# line_adapter.net
KiCad netlist of a schematic drawn in EAGLE
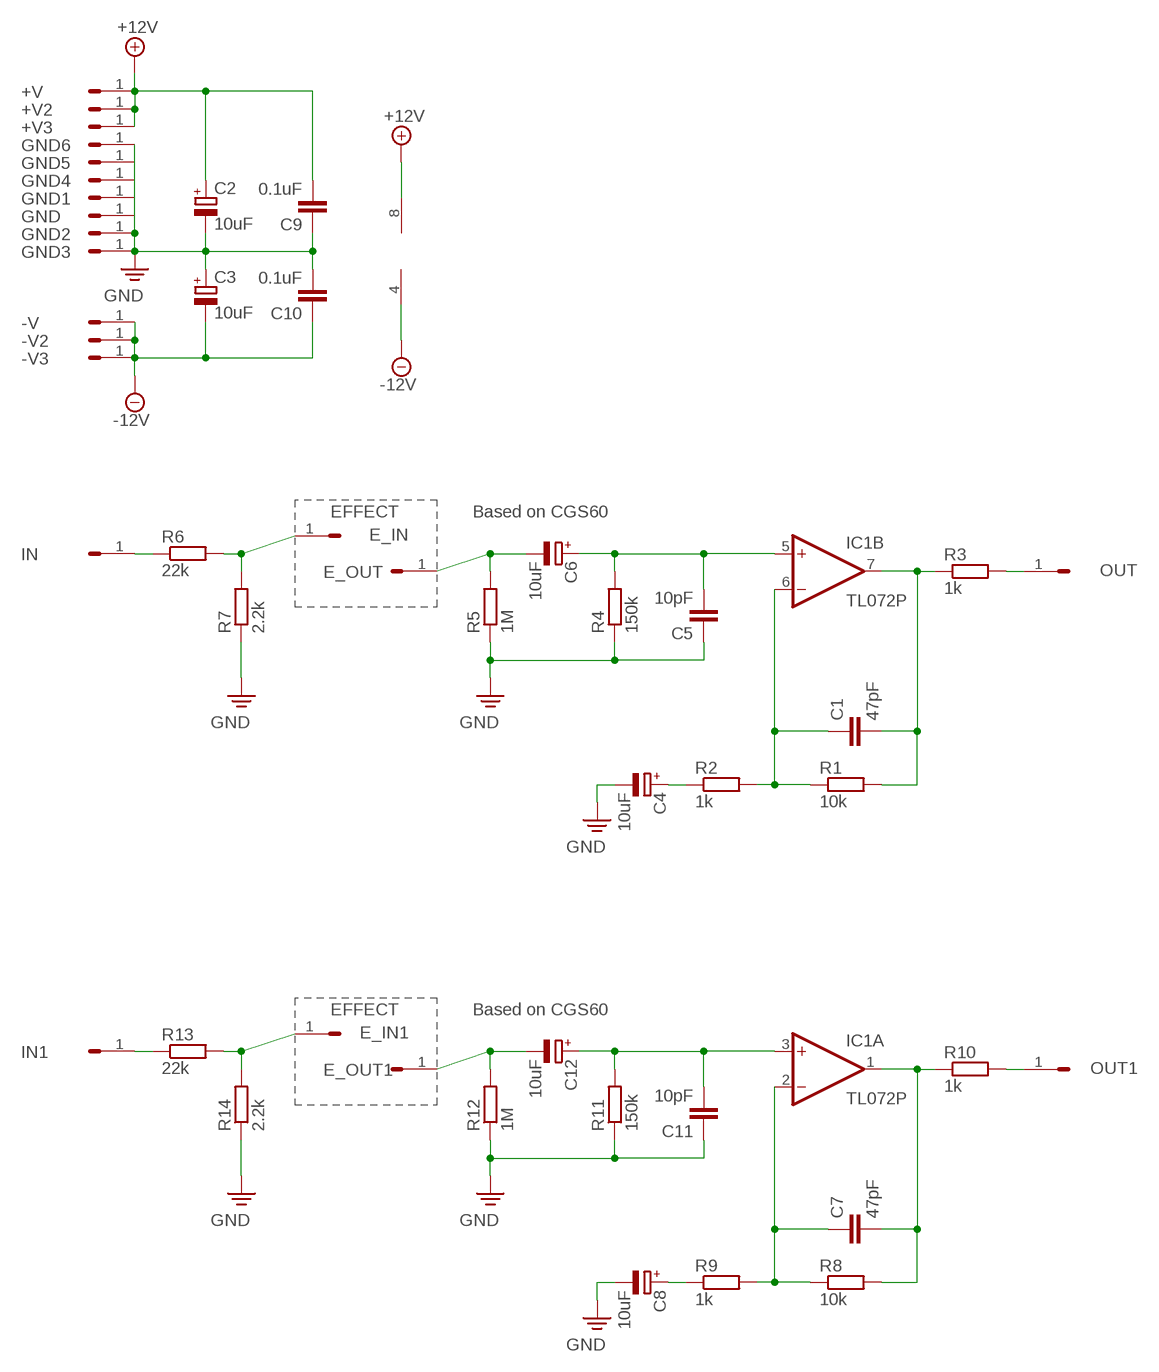
[diagram p0: schematic, sheet 1]

(export (version "E")
  (design (tool "Eeschema 10.0.6"))
  (components
    (comp (ref "+V")
      (value "HEADER/MALE/01")
      (footprint "eagle-import:HEADER_MALE_01")
      (fields (field (name "SPICEPREFIX") "X"))
      (libsource (lib "eagle-import") (part "HEADER/MALE/01"))
    )
    (comp (ref "+V2")
      (value "HEADER/MALE/01")
      (footprint "eagle-import:HEADER_MALE_01")
      (fields (field (name "SPICEPREFIX") "X"))
      (libsource (lib "eagle-import") (part "HEADER/MALE/01"))
    )
    (comp (ref "+V3")
      (value "HEADER/MALE/01")
      (footprint "eagle-import:HEADER_MALE_01")
      (fields (field (name "SPICEPREFIX") "X"))
      (libsource (lib "eagle-import") (part "HEADER/MALE/01"))
    )
    (comp (ref "-V")
      (value "HEADER/MALE/01")
      (footprint "eagle-import:HEADER_MALE_01")
      (fields (field (name "SPICEPREFIX") "X"))
      (libsource (lib "eagle-import") (part "HEADER/MALE/01"))
    )
    (comp (ref "-V2")
      (value "HEADER/MALE/01")
      (footprint "eagle-import:HEADER_MALE_01")
      (fields (field (name "SPICEPREFIX") "X"))
      (libsource (lib "eagle-import") (part "HEADER/MALE/01"))
    )
    (comp (ref "-V3")
      (value "HEADER/MALE/01")
      (footprint "eagle-import:HEADER_MALE_01")
      (fields (field (name "SPICEPREFIX") "X"))
      (libsource (lib "eagle-import") (part "HEADER/MALE/01"))
    )
    (comp (ref "C1")
      (value "47pF")
      (footprint "eagle-import:CERAMICDISC_5")
      (libsource (lib "eagle-import") (part "CAPACITORCERAMICDISC/5"))
    )
    (comp (ref "C2")
      (value "10uF")
      (footprint "eagle-import:E2,5-6")
      (fields (field (name "SPICEPREFIX") "C"))
      (libsource (lib "eagle-import") (part "CAPACITOR/POLARIZEDE2.5-6"))
    )
    (comp (ref "C3")
      (value "10uF")
      (footprint "eagle-import:E2,5-6")
      (fields (field (name "SPICEPREFIX") "C"))
      (libsource (lib "eagle-import") (part "CAPACITOR/POLARIZEDE2.5-6"))
    )
    (comp (ref "C4")
      (value "10uF")
      (footprint "eagle-import:E2,5-6")
      (fields (field (name "SPICEPREFIX") "C"))
      (libsource (lib "eagle-import") (part "CAPACITOR/POLARIZEDE2.5-6"))
    )
    (comp (ref "C5")
      (value "10pF")
      (footprint "eagle-import:CERAMICDISC_5")
      (libsource (lib "eagle-import") (part "CAPACITORCERAMICDISC/5"))
    )
    (comp (ref "C6")
      (value "10uF")
      (footprint "eagle-import:E2,5-6")
      (fields (field (name "SPICEPREFIX") "C"))
      (libsource (lib "eagle-import") (part "CAPACITOR/POLARIZEDE2.5-6"))
    )
    (comp (ref "C7")
      (value "47pF")
      (footprint "eagle-import:CERAMICDISC_5")
      (libsource (lib "eagle-import") (part "CAPACITORCERAMICDISC/5"))
    )
    (comp (ref "C8")
      (value "10uF")
      (footprint "eagle-import:E2,5-6")
      (fields (field (name "SPICEPREFIX") "C"))
      (libsource (lib "eagle-import") (part "CAPACITOR/POLARIZEDE2.5-6"))
    )
    (comp (ref "C9")
      (value "0.1uF")
      (footprint "eagle-import:CERAMICDISC_5")
      (libsource (lib "eagle-import") (part "CAPACITORCERAMICDISC/5"))
    )
    (comp (ref "C10")
      (value "0.1uF")
      (footprint "eagle-import:CERAMICDISC_5")
      (libsource (lib "eagle-import") (part "CAPACITORCERAMICDISC/5"))
    )
    (comp (ref "C11")
      (value "10pF")
      (footprint "eagle-import:CERAMICDISC_5")
      (libsource (lib "eagle-import") (part "CAPACITORCERAMICDISC/5"))
    )
    (comp (ref "C12")
      (value "10uF")
      (footprint "eagle-import:E2,5-6")
      (fields (field (name "SPICEPREFIX") "C"))
      (libsource (lib "eagle-import") (part "CAPACITOR/POLARIZEDE2.5-6"))
    )
    (comp (ref "E_IN")
      (value "HEADER/MALE/01")
      (footprint "eagle-import:HEADER_MALE_01")
      (fields (field (name "SPICEPREFIX") "X"))
      (libsource (lib "eagle-import") (part "HEADER/MALE/01"))
    )
    (comp (ref "E_IN1")
      (value "HEADER/MALE/01")
      (footprint "eagle-import:HEADER_MALE_01")
      (fields (field (name "SPICEPREFIX") "X"))
      (libsource (lib "eagle-import") (part "HEADER/MALE/01"))
    )
    (comp (ref "E_OUT")
      (value "HEADER/MALE/01")
      (footprint "eagle-import:HEADER_MALE_01")
      (fields (field (name "SPICEPREFIX") "X"))
      (libsource (lib "eagle-import") (part "HEADER/MALE/01"))
    )
    (comp (ref "E_OUT1")
      (value "HEADER/MALE/01")
      (footprint "eagle-import:HEADER_MALE_01")
      (fields (field (name "SPICEPREFIX") "X"))
      (libsource (lib "eagle-import") (part "HEADER/MALE/01"))
    )
    (comp (ref "GND")
      (value "HEADER/MALE/01")
      (footprint "eagle-import:HEADER_MALE_01")
      (fields (field (name "SPICEPREFIX") "X"))
      (libsource (lib "eagle-import") (part "HEADER/MALE/01"))
    )
    (comp (ref "GND1")
      (value "HEADER/MALE/01")
      (footprint "eagle-import:HEADER_MALE_01")
      (fields (field (name "SPICEPREFIX") "X"))
      (libsource (lib "eagle-import") (part "HEADER/MALE/01"))
    )
    (comp (ref "GND2")
      (value "HEADER/MALE/01")
      (footprint "eagle-import:HEADER_MALE_01")
      (fields (field (name "SPICEPREFIX") "X"))
      (libsource (lib "eagle-import") (part "HEADER/MALE/01"))
    )
    (comp (ref "GND3")
      (value "HEADER/MALE/01")
      (footprint "eagle-import:HEADER_MALE_01")
      (fields (field (name "SPICEPREFIX") "X"))
      (libsource (lib "eagle-import") (part "HEADER/MALE/01"))
    )
    (comp (ref "GND4")
      (value "HEADER/MALE/01")
      (footprint "eagle-import:HEADER_MALE_01")
      (fields (field (name "SPICEPREFIX") "X"))
      (libsource (lib "eagle-import") (part "HEADER/MALE/01"))
    )
    (comp (ref "GND5")
      (value "HEADER/MALE/01")
      (footprint "eagle-import:HEADER_MALE_01")
      (fields (field (name "SPICEPREFIX") "X"))
      (libsource (lib "eagle-import") (part "HEADER/MALE/01"))
    )
    (comp (ref "GND6")
      (value "HEADER/MALE/01")
      (footprint "eagle-import:HEADER_MALE_01")
      (fields (field (name "SPICEPREFIX") "X"))
      (libsource (lib "eagle-import") (part "HEADER/MALE/01"))
    )
    (comp (ref "IC1")
      (value "TL072P")
      (footprint "eagle-import:DIL08")
      (libsource (lib "eagle-import") (part "TL072P"))
    )
    (comp (ref "IN")
      (value "HEADER/MALE/01")
      (footprint "eagle-import:HEADER_MALE_01")
      (fields (field (name "SPICEPREFIX") "X"))
      (libsource (lib "eagle-import") (part "HEADER/MALE/01"))
    )
    (comp (ref "IN1")
      (value "HEADER/MALE/01")
      (footprint "eagle-import:HEADER_MALE_01")
      (fields (field (name "SPICEPREFIX") "X"))
      (libsource (lib "eagle-import") (part "HEADER/MALE/01"))
    )
    (comp (ref "OUT")
      (value "HEADER/MALE/01")
      (footprint "eagle-import:HEADER_MALE_01")
      (fields (field (name "SPICEPREFIX") "X"))
      (libsource (lib "eagle-import") (part "HEADER/MALE/01"))
    )
    (comp (ref "OUT1")
      (value "HEADER/MALE/01")
      (footprint "eagle-import:HEADER_MALE_01")
      (fields (field (name "SPICEPREFIX") "X"))
      (libsource (lib "eagle-import") (part "HEADER/MALE/01"))
    )
    (comp (ref "R1")
      (value "10k")
      (footprint "eagle-import:RESISTOR_7.5")
      (libsource (lib "eagle-import") (part "RESISTORRESISTOR/UPRIGHT/7.5"))
    )
    (comp (ref "R2")
      (value "1k")
      (footprint "eagle-import:RESISTOR_7.5")
      (libsource (lib "eagle-import") (part "RESISTORRESISTOR/UPRIGHT/7.5"))
    )
    (comp (ref "R3")
      (value "1k")
      (footprint "eagle-import:RESISTOR_7.5")
      (libsource (lib "eagle-import") (part "RESISTORRESISTOR/UPRIGHT/7.5"))
    )
    (comp (ref "R4")
      (value "150k")
      (footprint "eagle-import:RESISTOR_7.5")
      (libsource (lib "eagle-import") (part "RESISTORRESISTOR/UPRIGHT/7.5"))
    )
    (comp (ref "R5")
      (value "1M")
      (footprint "eagle-import:RESISTOR_7.5")
      (libsource (lib "eagle-import") (part "RESISTORRESISTOR/UPRIGHT/7.5"))
    )
    (comp (ref "R6")
      (value "22k")
      (footprint "eagle-import:RESISTOR_7.5")
      (libsource (lib "eagle-import") (part "RESISTORRESISTOR/UPRIGHT/7.5"))
    )
    (comp (ref "R7")
      (value "2.2k")
      (footprint "eagle-import:RESISTOR_7.5")
      (libsource (lib "eagle-import") (part "RESISTORRESISTOR/UPRIGHT/7.5"))
    )
    (comp (ref "R8")
      (value "10k")
      (footprint "eagle-import:RESISTOR_7.5")
      (libsource (lib "eagle-import") (part "RESISTORRESISTOR/UPRIGHT/7.5"))
    )
    (comp (ref "R9")
      (value "1k")
      (footprint "eagle-import:RESISTOR_7.5")
      (libsource (lib "eagle-import") (part "RESISTORRESISTOR/UPRIGHT/7.5"))
    )
    (comp (ref "R10")
      (value "1k")
      (footprint "eagle-import:RESISTOR_7.5")
      (libsource (lib "eagle-import") (part "RESISTORRESISTOR/UPRIGHT/7.5"))
    )
    (comp (ref "R11")
      (value "150k")
      (footprint "eagle-import:RESISTOR_7.5")
      (libsource (lib "eagle-import") (part "RESISTORRESISTOR/UPRIGHT/7.5"))
    )
    (comp (ref "R12")
      (value "1M")
      (footprint "eagle-import:RESISTOR_7.5")
      (libsource (lib "eagle-import") (part "RESISTORRESISTOR/UPRIGHT/7.5"))
    )
    (comp (ref "R13")
      (value "22k")
      (footprint "eagle-import:RESISTOR_7.5")
      (libsource (lib "eagle-import") (part "RESISTORRESISTOR/UPRIGHT/7.5"))
    )
    (comp (ref "R14")
      (value "2.2k")
      (footprint "eagle-import:RESISTOR_7.5")
      (libsource (lib "eagle-import") (part "RESISTORRESISTOR/UPRIGHT/7.5"))
    )
  )
  (nets
    (net (code "1") (name "+12V") (class "Default")
      (node (ref "+V") (pin "1") (pinfunction "3_1") (pintype "passive"))
      (node (ref "+V2") (pin "1") (pinfunction "3_1") (pintype "passive"))
      (node (ref "+V3") (pin "1") (pinfunction "3_1") (pintype "passive"))
      (node (ref "C2") (pin "+") (pinfunction "+_+") (pintype "passive"))
      (node (ref "C9") (pin "2") (pinfunction "2_2") (pintype "passive"))
      (node (ref "IC1") (pin "8") (pinfunction "V+_8") (pintype "power_in"))
    )
    (net (code "2") (name "-12V") (class "Default")
      (node (ref "-V") (pin "1") (pinfunction "3_1") (pintype "passive"))
      (node (ref "-V2") (pin "1") (pinfunction "3_1") (pintype "passive"))
      (node (ref "-V3") (pin "1") (pinfunction "3_1") (pintype "passive"))
      (node (ref "C10") (pin "1") (pinfunction "1_1") (pintype "passive"))
      (node (ref "C3") (pin "-") (pinfunction "-_-") (pintype "passive"))
      (node (ref "IC1") (pin "4") (pinfunction "V-_4") (pintype "power_in"))
    )
    (net (code "3") (name "GND") (class "Default")
      (node (ref "C10") (pin "2") (pinfunction "2_2") (pintype "passive"))
      (node (ref "C11") (pin "1") (pinfunction "1_1") (pintype "passive"))
      (node (ref "C2") (pin "-") (pinfunction "-_-") (pintype "passive"))
      (node (ref "C3") (pin "+") (pinfunction "+_+") (pintype "passive"))
      (node (ref "C4") (pin "-") (pinfunction "-_-") (pintype "passive"))
      (node (ref "C5") (pin "1") (pinfunction "1_1") (pintype "passive"))
      (node (ref "C8") (pin "-") (pinfunction "-_-") (pintype "passive"))
      (node (ref "C9") (pin "1") (pinfunction "1_1") (pintype "passive"))
      (node (ref "GND") (pin "1") (pinfunction "3_1") (pintype "passive"))
      (node (ref "GND1") (pin "1") (pinfunction "3_1") (pintype "passive"))
      (node (ref "GND2") (pin "1") (pinfunction "3_1") (pintype "passive"))
      (node (ref "GND3") (pin "1") (pinfunction "3_1") (pintype "passive"))
      (node (ref "GND4") (pin "1") (pinfunction "3_1") (pintype "passive"))
      (node (ref "GND5") (pin "1") (pinfunction "3_1") (pintype "passive"))
      (node (ref "GND6") (pin "1") (pinfunction "3_1") (pintype "passive"))
      (node (ref "R11") (pin "1") (pinfunction "1_1") (pintype "passive"))
      (node (ref "R12") (pin "1") (pinfunction "1_1") (pintype "passive"))
      (node (ref "R14") (pin "1") (pinfunction "1_1") (pintype "passive"))
      (node (ref "R4") (pin "1") (pinfunction "1_1") (pintype "passive"))
      (node (ref "R5") (pin "1") (pinfunction "1_1") (pintype "passive"))
      (node (ref "R7") (pin "1") (pinfunction "1_1") (pintype "passive"))
    )
    (net (code "4") (name "Net-(C4-Pad+)") (class "Default")
      (node (ref "C4") (pin "+") (pinfunction "+_+") (pintype "passive"))
      (node (ref "R2") (pin "1") (pinfunction "1_1") (pintype "passive"))
    )
    (net (code "5") (name "Net-(C8-Pad+)") (class "Default")
      (node (ref "C8") (pin "+") (pinfunction "+_+") (pintype "passive"))
      (node (ref "R9") (pin "1") (pinfunction "1_1") (pintype "passive"))
    )
    (net (code "6") (name "Net-(E_IN-3)") (class "Default")
      (node (ref "E_IN") (pin "1") (pinfunction "3_1") (pintype "passive"))
      (node (ref "R6") (pin "2") (pinfunction "2_2") (pintype "passive"))
      (node (ref "R7") (pin "2") (pinfunction "2_2") (pintype "passive"))
    )
    (net (code "7") (name "Net-(E_IN1-3)") (class "Default")
      (node (ref "E_IN1") (pin "1") (pinfunction "3_1") (pintype "passive"))
      (node (ref "R13") (pin "2") (pinfunction "2_2") (pintype "passive"))
      (node (ref "R14") (pin "2") (pinfunction "2_2") (pintype "passive"))
    )
    (net (code "8") (name "Net-(E_OUT-3)") (class "Default")
      (node (ref "C6") (pin "-") (pinfunction "-_-") (pintype "passive"))
      (node (ref "E_OUT") (pin "1") (pinfunction "3_1") (pintype "passive"))
      (node (ref "R5") (pin "2") (pinfunction "2_2") (pintype "passive"))
    )
    (net (code "9") (name "Net-(E_OUT1-3)") (class "Default")
      (node (ref "C12") (pin "-") (pinfunction "-_-") (pintype "passive"))
      (node (ref "E_OUT1") (pin "1") (pinfunction "3_1") (pintype "passive"))
      (node (ref "R12") (pin "2") (pinfunction "2_2") (pintype "passive"))
    )
    (net (code "10") (name "Net-(IC1A-+IN)") (class "Default")
      (node (ref "C11") (pin "2") (pinfunction "2_2") (pintype "passive"))
      (node (ref "C12") (pin "+") (pinfunction "+_+") (pintype "passive"))
      (node (ref "IC1") (pin "3") (pinfunction "+IN_3") (pintype "input"))
      (node (ref "R11") (pin "2") (pinfunction "2_2") (pintype "passive"))
    )
    (net (code "11") (name "Net-(IC1A--IN)") (class "Default")
      (node (ref "C7") (pin "1") (pinfunction "1_1") (pintype "passive"))
      (node (ref "IC1") (pin "2") (pinfunction "-IN_2") (pintype "input"))
      (node (ref "R8") (pin "1") (pinfunction "1_1") (pintype "passive"))
      (node (ref "R9") (pin "2") (pinfunction "2_2") (pintype "passive"))
    )
    (net (code "12") (name "Net-(IC1A-OUT)") (class "Default")
      (node (ref "C7") (pin "2") (pinfunction "2_2") (pintype "passive"))
      (node (ref "IC1") (pin "1") (pinfunction "OUT_1") (pintype "output"))
      (node (ref "R10") (pin "1") (pinfunction "1_1") (pintype "passive"))
      (node (ref "R8") (pin "2") (pinfunction "2_2") (pintype "passive"))
    )
    (net (code "13") (name "Net-(IC1B-+IN)") (class "Default")
      (node (ref "C5") (pin "2") (pinfunction "2_2") (pintype "passive"))
      (node (ref "C6") (pin "+") (pinfunction "+_+") (pintype "passive"))
      (node (ref "IC1") (pin "5") (pinfunction "+IN_5") (pintype "input"))
      (node (ref "R4") (pin "2") (pinfunction "2_2") (pintype "passive"))
    )
    (net (code "14") (name "Net-(IC1B--IN)") (class "Default")
      (node (ref "C1") (pin "1") (pinfunction "1_1") (pintype "passive"))
      (node (ref "IC1") (pin "6") (pinfunction "-IN_6") (pintype "input"))
      (node (ref "R1") (pin "1") (pinfunction "1_1") (pintype "passive"))
      (node (ref "R2") (pin "2") (pinfunction "2_2") (pintype "passive"))
    )
    (net (code "15") (name "Net-(IC1B-OUT)") (class "Default")
      (node (ref "C1") (pin "2") (pinfunction "2_2") (pintype "passive"))
      (node (ref "IC1") (pin "7") (pinfunction "OUT_7") (pintype "output"))
      (node (ref "R1") (pin "2") (pinfunction "2_2") (pintype "passive"))
      (node (ref "R3") (pin "1") (pinfunction "1_1") (pintype "passive"))
    )
    (net (code "16") (name "Net-(IN-3)") (class "Default")
      (node (ref "IN") (pin "1") (pinfunction "3_1") (pintype "passive"))
      (node (ref "R6") (pin "1") (pinfunction "1_1") (pintype "passive"))
    )
    (net (code "17") (name "Net-(IN1-3)") (class "Default")
      (node (ref "IN1") (pin "1") (pinfunction "3_1") (pintype "passive"))
      (node (ref "R13") (pin "1") (pinfunction "1_1") (pintype "passive"))
    )
    (net (code "18") (name "Net-(OUT-3)") (class "Default")
      (node (ref "OUT") (pin "1") (pinfunction "3_1") (pintype "passive"))
      (node (ref "R3") (pin "2") (pinfunction "2_2") (pintype "passive"))
    )
    (net (code "19") (name "Net-(OUT1-3)") (class "Default")
      (node (ref "OUT1") (pin "1") (pinfunction "3_1") (pintype "passive"))
      (node (ref "R10") (pin "2") (pinfunction "2_2") (pintype "passive"))
    )
  )
)
